# dynalo_v_dual.net
KiCad netlist of a schematic drawn in EAGLE
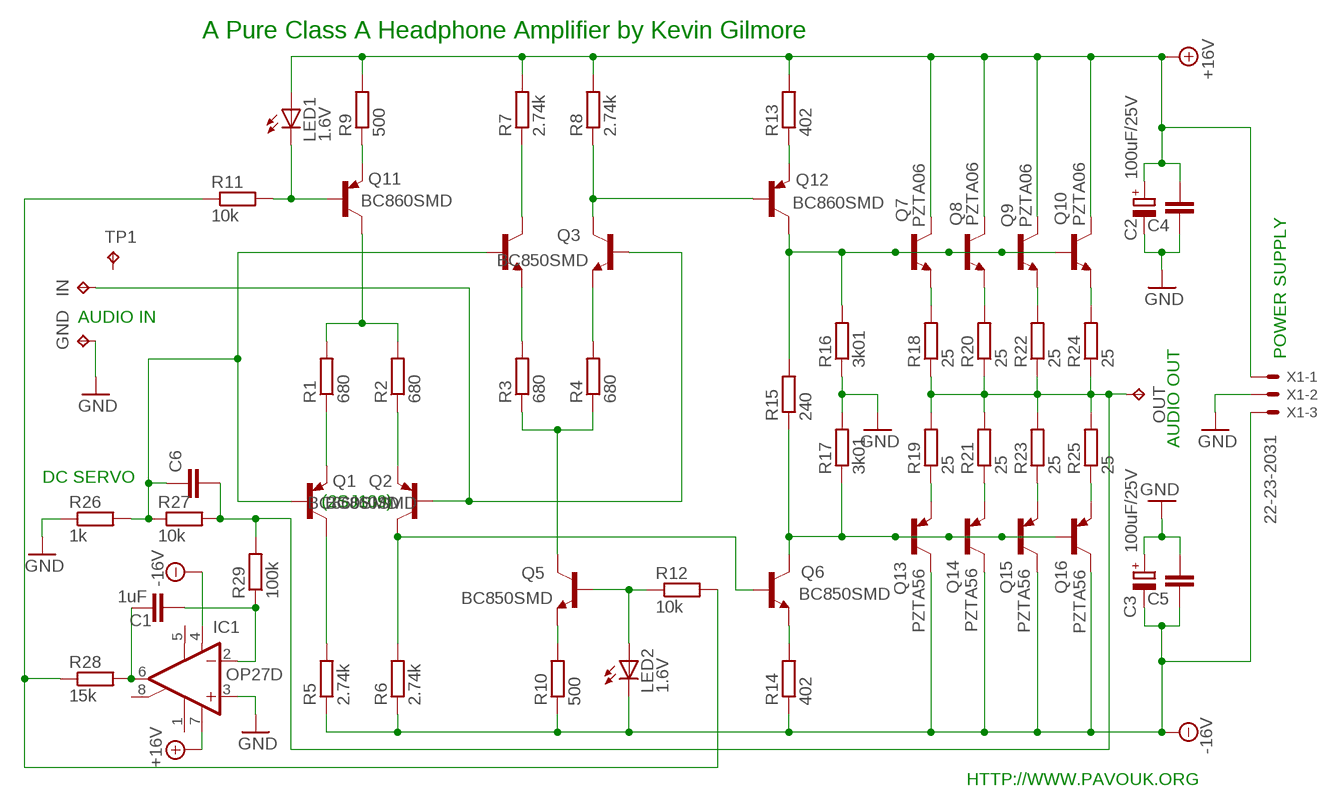
[diagram p0: schematic, sheet 1]

(export (version "E")
  (design (tool "Eeschema 10.0.6"))
  (components
    (comp (ref "C1")
      (value "1uF")
      (footprint "eagle-import:C1206")
      (libsource (lib "eagle-import") (part "C-EUC1206"))
    )
    (comp (ref "C2")
      (value "100uF/25V")
      (footprint "eagle-import:E3,5-8")
      (libsource (lib "eagle-import") (part "CPOL-EUE3.5-8"))
    )
    (comp (ref "C3")
      (value "100uF/25V")
      (footprint "eagle-import:E3,5-8")
      (libsource (lib "eagle-import") (part "CPOL-EUE3.5-8"))
    )
    (comp (ref "C4")
      (value "C-EUC1206")
      (footprint "eagle-import:C1206")
      (libsource (lib "eagle-import") (part "C-EUC1206"))
    )
    (comp (ref "C5")
      (value "C-EUC1206")
      (footprint "eagle-import:C1206")
      (libsource (lib "eagle-import") (part "C-EUC1206"))
    )
    (comp (ref "C6")
      (value "C-EUC1206")
      (footprint "eagle-import:C1206")
      (libsource (lib "eagle-import") (part "C-EUC1206"))
    )
    (comp (ref "GND")
      (value "TPPAD1-13")
      (footprint "eagle-import:P1-13")
      (libsource (lib "eagle-import") (part "TPPAD1-13"))
    )
    (comp (ref "IC1")
      (value "OP27D")
      (footprint "eagle-import:SO08")
      (libsource (lib "eagle-import") (part "OP27D"))
    )
    (comp (ref "IN")
      (value "TPPAD1-13")
      (footprint "eagle-import:P1-13")
      (libsource (lib "eagle-import") (part "TPPAD1-13"))
    )
    (comp (ref "LED1")
      (value "1.6V")
      (footprint "eagle-import:CHIPLED_1206")
      (libsource (lib "eagle-import") (part "LEDCHIPLED_1206"))
    )
    (comp (ref "LED2")
      (value "1.6V")
      (footprint "eagle-import:CHIPLED_1206")
      (libsource (lib "eagle-import") (part "LEDCHIPLED_1206"))
    )
    (comp (ref "OUT")
      (value "TPPAD1-13")
      (footprint "eagle-import:P1-13")
      (libsource (lib "eagle-import") (part "TPPAD1-13"))
    )
    (comp (ref "Q1")
      (value "BC860SMD")
      (footprint "eagle-import:SOT23-BEC")
      (libsource (lib "eagle-import") (part "BC860SMDC"))
    )
    (comp (ref "Q2")
      (value "BC860SMD")
      (footprint "eagle-import:SOT23-BEC")
      (libsource (lib "eagle-import") (part "BC860SMDC"))
    )
    (comp (ref "Q3")
      (value "BC850SMD")
      (footprint "eagle-import:SOT23-BEC")
      (libsource (lib "eagle-import") (part "BC850SMD"))
    )
    (comp (ref "Q4")
      (value "BC850SMD")
      (footprint "eagle-import:SOT23-BEC")
      (libsource (lib "eagle-import") (part "BC850SMD"))
    )
    (comp (ref "Q5")
      (value "BC850SMD")
      (footprint "eagle-import:SOT23-BEC")
      (libsource (lib "eagle-import") (part "BC850SMD"))
    )
    (comp (ref "Q6")
      (value "BC850SMD")
      (footprint "eagle-import:SOT23-BEC")
      (libsource (lib "eagle-import") (part "BC850SMD"))
    )
    (comp (ref "Q7")
      (value "PZTA06")
      (footprint "eagle-import:SOT223R_INFINEON")
      (libsource (lib "eagle-import") (part "PZTA06"))
    )
    (comp (ref "Q8")
      (value "PZTA06")
      (footprint "eagle-import:SOT223R_INFINEON")
      (libsource (lib "eagle-import") (part "PZTA06"))
    )
    (comp (ref "Q9")
      (value "PZTA06")
      (footprint "eagle-import:SOT223R_INFINEON")
      (libsource (lib "eagle-import") (part "PZTA06"))
    )
    (comp (ref "Q10")
      (value "PZTA06")
      (footprint "eagle-import:SOT223R_INFINEON")
      (libsource (lib "eagle-import") (part "PZTA06"))
    )
    (comp (ref "Q11")
      (value "BC860SMD")
      (footprint "eagle-import:SOT23-BEC")
      (libsource (lib "eagle-import") (part "BC860SMDC"))
    )
    (comp (ref "Q12")
      (value "BC860SMD")
      (footprint "eagle-import:SOT23-BEC")
      (libsource (lib "eagle-import") (part "BC860SMDC"))
    )
    (comp (ref "Q13")
      (value "PZTA56")
      (footprint "eagle-import:SOT223R_INFINEON")
      (libsource (lib "eagle-import") (part "PZTA56"))
    )
    (comp (ref "Q14")
      (value "PZTA56")
      (footprint "eagle-import:SOT223R_INFINEON")
      (libsource (lib "eagle-import") (part "PZTA56"))
    )
    (comp (ref "Q15")
      (value "PZTA56")
      (footprint "eagle-import:SOT223R_INFINEON")
      (libsource (lib "eagle-import") (part "PZTA56"))
    )
    (comp (ref "Q16")
      (value "PZTA56")
      (footprint "eagle-import:SOT223R_INFINEON")
      (libsource (lib "eagle-import") (part "PZTA56"))
    )
    (comp (ref "R1")
      (value "680")
      (footprint "eagle-import:MINI_MELF-0204W")
      (libsource (lib "eagle-import") (part "R-EU_MELF0204W"))
    )
    (comp (ref "R2")
      (value "680")
      (footprint "eagle-import:MINI_MELF-0204W")
      (libsource (lib "eagle-import") (part "R-EU_MELF0204W"))
    )
    (comp (ref "R3")
      (value "680")
      (footprint "eagle-import:MINI_MELF-0204W")
      (libsource (lib "eagle-import") (part "R-EU_MELF0204W"))
    )
    (comp (ref "R4")
      (value "680")
      (footprint "eagle-import:MINI_MELF-0204W")
      (libsource (lib "eagle-import") (part "R-EU_MELF0204W"))
    )
    (comp (ref "R5")
      (value "2.74k")
      (footprint "eagle-import:MINI_MELF-0204W")
      (libsource (lib "eagle-import") (part "R-EU_MELF0204W"))
    )
    (comp (ref "R6")
      (value "2.74k")
      (footprint "eagle-import:MINI_MELF-0204W")
      (libsource (lib "eagle-import") (part "R-EU_MELF0204W"))
    )
    (comp (ref "R7")
      (value "2.74k")
      (footprint "eagle-import:MINI_MELF-0204W")
      (libsource (lib "eagle-import") (part "R-EU_MELF0204W"))
    )
    (comp (ref "R8")
      (value "2.74k")
      (footprint "eagle-import:MINI_MELF-0204W")
      (libsource (lib "eagle-import") (part "R-EU_MELF0204W"))
    )
    (comp (ref "R9")
      (value "500")
      (footprint "eagle-import:MINI_MELF-0204W")
      (libsource (lib "eagle-import") (part "R-EU_MELF0204W"))
    )
    (comp (ref "R10")
      (value "500")
      (footprint "eagle-import:MINI_MELF-0204W")
      (libsource (lib "eagle-import") (part "R-EU_MELF0204W"))
    )
    (comp (ref "R11")
      (value "10k")
      (footprint "eagle-import:MINI_MELF-0204W")
      (libsource (lib "eagle-import") (part "R-EU_MELF0204W"))
    )
    (comp (ref "R12")
      (value "10k")
      (footprint "eagle-import:MINI_MELF-0204W")
      (libsource (lib "eagle-import") (part "R-EU_MELF0204W"))
    )
    (comp (ref "R13")
      (value "402")
      (footprint "eagle-import:MINI_MELF-0204W")
      (libsource (lib "eagle-import") (part "R-EU_MELF0204W"))
    )
    (comp (ref "R14")
      (value "402")
      (footprint "eagle-import:MINI_MELF-0204W")
      (libsource (lib "eagle-import") (part "R-EU_MELF0204W"))
    )
    (comp (ref "R15")
      (value "240")
      (footprint "eagle-import:MINI_MELF-0204W")
      (libsource (lib "eagle-import") (part "R-EU_MELF0204W"))
    )
    (comp (ref "R16")
      (value "3k01")
      (footprint "eagle-import:MINI_MELF-0204W")
      (libsource (lib "eagle-import") (part "R-EU_MELF0204W"))
    )
    (comp (ref "R17")
      (value "3k01")
      (footprint "eagle-import:MINI_MELF-0204W")
      (libsource (lib "eagle-import") (part "R-EU_MELF0204W"))
    )
    (comp (ref "R18")
      (value "25")
      (footprint "eagle-import:MINI_MELF-0204W")
      (libsource (lib "eagle-import") (part "R-EU_MELF0204W"))
    )
    (comp (ref "R19")
      (value "25")
      (footprint "eagle-import:MINI_MELF-0204W")
      (libsource (lib "eagle-import") (part "R-EU_MELF0204W"))
    )
    (comp (ref "R20")
      (value "25")
      (footprint "eagle-import:MINI_MELF-0204W")
      (libsource (lib "eagle-import") (part "R-EU_MELF0204W"))
    )
    (comp (ref "R21")
      (value "25")
      (footprint "eagle-import:MINI_MELF-0204W")
      (libsource (lib "eagle-import") (part "R-EU_MELF0204W"))
    )
    (comp (ref "R22")
      (value "25")
      (footprint "eagle-import:MINI_MELF-0204W")
      (libsource (lib "eagle-import") (part "R-EU_MELF0204W"))
    )
    (comp (ref "R23")
      (value "25")
      (footprint "eagle-import:MINI_MELF-0204W")
      (libsource (lib "eagle-import") (part "R-EU_MELF0204W"))
    )
    (comp (ref "R24")
      (value "25")
      (footprint "eagle-import:MINI_MELF-0204W")
      (libsource (lib "eagle-import") (part "R-EU_MELF0204W"))
    )
    (comp (ref "R25")
      (value "25")
      (footprint "eagle-import:MINI_MELF-0204W")
      (libsource (lib "eagle-import") (part "R-EU_MELF0204W"))
    )
    (comp (ref "R26")
      (value "1k")
      (footprint "eagle-import:MINI_MELF-0204W")
      (libsource (lib "eagle-import") (part "R-EU_MELF0204W"))
    )
    (comp (ref "R27")
      (value "10k")
      (footprint "eagle-import:MINI_MELF-0204W")
      (libsource (lib "eagle-import") (part "R-EU_MELF0204W"))
    )
    (comp (ref "R28")
      (value "15k")
      (footprint "eagle-import:MINI_MELF-0204W")
      (libsource (lib "eagle-import") (part "R-EU_MELF0204W"))
    )
    (comp (ref "R29")
      (value "100k")
      (footprint "eagle-import:MINI_MELF-0204W")
      (libsource (lib "eagle-import") (part "R-EU_MELF0204W"))
    )
    (comp (ref "TP1")
      (value "TPPAD1-13")
      (footprint "eagle-import:P1-13")
      (libsource (lib "eagle-import") (part "TPPAD1-13"))
    )
    (comp (ref "X1")
      (value "22-23-2031")
      (footprint "eagle-import:22-23-2031")
      (libsource (lib "eagle-import") (part "22-23-2031"))
    )
  )
  (nets
    (net (code "1") (name "+16V") (class "Default")
      (node (ref "C2") (pin "+") (pinfunction "+_+") (pintype "passive"))
      (node (ref "C4") (pin "2") (pinfunction "2_2") (pintype "passive"))
      (node (ref "IC1") (pin "7") (pinfunction "V+_7") (pintype "power_in"))
      (node (ref "LED1") (pin "A") (pinfunction "A_A") (pintype "passive"))
      (node (ref "Q10") (pin "2") (pinfunction "C_2") (pintype "passive"))
      (node (ref "Q10") (pin "4") (pinfunction "C_4") (pintype "passive"))
      (node (ref "Q7") (pin "2") (pinfunction "C_2") (pintype "passive"))
      (node (ref "Q7") (pin "4") (pinfunction "C_4") (pintype "passive"))
      (node (ref "Q8") (pin "2") (pinfunction "C_2") (pintype "passive"))
      (node (ref "Q8") (pin "4") (pinfunction "C_4") (pintype "passive"))
      (node (ref "Q9") (pin "2") (pinfunction "C_2") (pintype "passive"))
      (node (ref "Q9") (pin "4") (pinfunction "C_4") (pintype "passive"))
      (node (ref "R13") (pin "2") (pinfunction "2_2") (pintype "passive"))
      (node (ref "R7") (pin "2") (pinfunction "2_2") (pintype "passive"))
      (node (ref "R8") (pin "2") (pinfunction "2_2") (pintype "passive"))
      (node (ref "R9") (pin "2") (pinfunction "2_2") (pintype "passive"))
      (node (ref "X1") (pin "1") (pinfunction "S_1") (pintype "passive"))
    )
    (net (code "2") (name "-16V") (class "Default")
      (node (ref "C3") (pin "-") (pinfunction "-_-") (pintype "passive"))
      (node (ref "C5") (pin "1") (pinfunction "1_1") (pintype "passive"))
      (node (ref "IC1") (pin "4") (pinfunction "V-_4") (pintype "power_in"))
      (node (ref "LED2") (pin "C") (pinfunction "C_C") (pintype "passive"))
      (node (ref "Q13") (pin "2") (pinfunction "C_2") (pintype "passive"))
      (node (ref "Q13") (pin "4") (pinfunction "C_4") (pintype "passive"))
      (node (ref "Q14") (pin "2") (pinfunction "C_2") (pintype "passive"))
      (node (ref "Q14") (pin "4") (pinfunction "C_4") (pintype "passive"))
      (node (ref "Q15") (pin "2") (pinfunction "C_2") (pintype "passive"))
      (node (ref "Q15") (pin "4") (pinfunction "C_4") (pintype "passive"))
      (node (ref "Q16") (pin "2") (pinfunction "C_2") (pintype "passive"))
      (node (ref "Q16") (pin "4") (pinfunction "C_4") (pintype "passive"))
      (node (ref "R10") (pin "1") (pinfunction "1_1") (pintype "passive"))
      (node (ref "R14") (pin "1") (pinfunction "1_1") (pintype "passive"))
      (node (ref "R5") (pin "1") (pinfunction "1_1") (pintype "passive"))
      (node (ref "R6") (pin "1") (pinfunction "1_1") (pintype "passive"))
      (node (ref "X1") (pin "3") (pinfunction "S_3") (pintype "passive"))
    )
    (net (code "3") (name "GND") (class "Default")
      (node (ref "C2") (pin "-") (pinfunction "-_-") (pintype "passive"))
      (node (ref "C3") (pin "+") (pinfunction "+_+") (pintype "passive"))
      (node (ref "C4") (pin "1") (pinfunction "1_1") (pintype "passive"))
      (node (ref "C5") (pin "2") (pinfunction "2_2") (pintype "passive"))
      (node (ref "GND") (pin "TP") (pinfunction "TP_TP") (pintype "input"))
      (node (ref "IC1") (pin "3") (pinfunction "+IN_3") (pintype "input"))
      (node (ref "R16") (pin "1") (pinfunction "1_1") (pintype "passive"))
      (node (ref "R17") (pin "2") (pinfunction "2_2") (pintype "passive"))
      (node (ref "R26") (pin "1") (pinfunction "1_1") (pintype "passive"))
      (node (ref "X1") (pin "2") (pinfunction "S_2") (pintype "passive"))
    )
    (net (code "4") (name "Net-(C6-Pad1)") (class "Default")
      (node (ref "C6") (pin "1") (pinfunction "1_1") (pintype "passive"))
      (node (ref "Q1") (pin "B") (pinfunction "B_B") (pintype "passive"))
      (node (ref "Q4") (pin "B") (pinfunction "B_B") (pintype "passive"))
      (node (ref "R26") (pin "2") (pinfunction "2_2") (pintype "passive"))
      (node (ref "R27") (pin "1") (pinfunction "1_1") (pintype "passive"))
    )
    (net (code "5") (name "Net-(C6-Pad2)") (class "Default")
      (node (ref "C6") (pin "2") (pinfunction "2_2") (pintype "passive"))
      (node (ref "OUT") (pin "TP") (pinfunction "TP_TP") (pintype "input"))
      (node (ref "R18") (pin "1") (pinfunction "1_1") (pintype "passive"))
      (node (ref "R19") (pin "2") (pinfunction "2_2") (pintype "passive"))
      (node (ref "R20") (pin "1") (pinfunction "1_1") (pintype "passive"))
      (node (ref "R21") (pin "2") (pinfunction "2_2") (pintype "passive"))
      (node (ref "R22") (pin "1") (pinfunction "1_1") (pintype "passive"))
      (node (ref "R23") (pin "2") (pinfunction "2_2") (pintype "passive"))
      (node (ref "R24") (pin "1") (pinfunction "1_1") (pintype "passive"))
      (node (ref "R25") (pin "2") (pinfunction "2_2") (pintype "passive"))
      (node (ref "R27") (pin "2") (pinfunction "2_2") (pintype "passive"))
      (node (ref "R29") (pin "2") (pinfunction "2_2") (pintype "passive"))
    )
    (net (code "6") (name "Net-(IC1--IN)") (class "Default")
      (node (ref "C1") (pin "2") (pinfunction "2_2") (pintype "passive"))
      (node (ref "IC1") (pin "2") (pinfunction "-IN_2") (pintype "input"))
      (node (ref "R29") (pin "1") (pinfunction "1_1") (pintype "passive"))
    )
    (net (code "7") (name "Net-(IC1-OUT)") (class "Default")
      (node (ref "C1") (pin "1") (pinfunction "1_1") (pintype "passive"))
      (node (ref "IC1") (pin "6") (pinfunction "OUT_6") (pintype "output"))
      (node (ref "R28") (pin "2") (pinfunction "2_2") (pintype "passive"))
    )
    (net (code "8") (name "Net-(IN-PadTP)") (class "Default")
      (node (ref "IN") (pin "TP") (pinfunction "TP_TP") (pintype "input"))
      (node (ref "Q2") (pin "B") (pinfunction "B_B") (pintype "passive"))
      (node (ref "Q3") (pin "B") (pinfunction "B_B") (pintype "passive"))
    )
    (net (code "9") (name "Net-(LED1-PadC)") (class "Default")
      (node (ref "LED1") (pin "C") (pinfunction "C_C") (pintype "passive"))
      (node (ref "Q11") (pin "B") (pinfunction "B_B") (pintype "passive"))
      (node (ref "R11") (pin "2") (pinfunction "2_2") (pintype "passive"))
    )
    (net (code "10") (name "Net-(LED2-PadA)") (class "Default")
      (node (ref "LED2") (pin "A") (pinfunction "A_A") (pintype "passive"))
      (node (ref "Q5") (pin "B") (pinfunction "B_B") (pintype "passive"))
      (node (ref "R12") (pin "1") (pinfunction "1_1") (pintype "passive"))
    )
    (net (code "11") (name "Net-(Q1-PadC)") (class "Default")
      (node (ref "Q1") (pin "C") (pinfunction "C_C") (pintype "passive"))
      (node (ref "R5") (pin "2") (pinfunction "2_2") (pintype "passive"))
    )
    (net (code "12") (name "Net-(Q1-PadE)") (class "Default")
      (node (ref "Q1") (pin "E") (pinfunction "E_E") (pintype "passive"))
      (node (ref "R1") (pin "1") (pinfunction "1_1") (pintype "passive"))
    )
    (net (code "13") (name "Net-(Q2-PadC)") (class "Default")
      (node (ref "Q2") (pin "C") (pinfunction "C_C") (pintype "passive"))
      (node (ref "Q6") (pin "B") (pinfunction "B_B") (pintype "passive"))
      (node (ref "R6") (pin "2") (pinfunction "2_2") (pintype "passive"))
    )
    (net (code "14") (name "Net-(Q2-PadE)") (class "Default")
      (node (ref "Q2") (pin "E") (pinfunction "E_E") (pintype "passive"))
      (node (ref "R2") (pin "1") (pinfunction "1_1") (pintype "passive"))
    )
    (net (code "15") (name "Net-(Q3-PadE)") (class "Default")
      (node (ref "Q3") (pin "E") (pinfunction "E_E") (pintype "passive"))
      (node (ref "R4") (pin "2") (pinfunction "2_2") (pintype "passive"))
    )
    (net (code "16") (name "Net-(Q4-PadC)") (class "Default")
      (node (ref "Q4") (pin "C") (pinfunction "C_C") (pintype "passive"))
      (node (ref "R7") (pin "1") (pinfunction "1_1") (pintype "passive"))
    )
    (net (code "17") (name "Net-(Q4-PadE)") (class "Default")
      (node (ref "Q4") (pin "E") (pinfunction "E_E") (pintype "passive"))
      (node (ref "R3") (pin "2") (pinfunction "2_2") (pintype "passive"))
    )
    (net (code "18") (name "Net-(Q5-PadC)") (class "Default")
      (node (ref "Q5") (pin "C") (pinfunction "C_C") (pintype "passive"))
      (node (ref "R3") (pin "1") (pinfunction "1_1") (pintype "passive"))
      (node (ref "R4") (pin "1") (pinfunction "1_1") (pintype "passive"))
    )
    (net (code "19") (name "Net-(Q5-PadE)") (class "Default")
      (node (ref "Q5") (pin "E") (pinfunction "E_E") (pintype "passive"))
      (node (ref "R10") (pin "2") (pinfunction "2_2") (pintype "passive"))
    )
    (net (code "20") (name "Net-(Q6-PadE)") (class "Default")
      (node (ref "Q6") (pin "E") (pinfunction "E_E") (pintype "passive"))
      (node (ref "R14") (pin "2") (pinfunction "2_2") (pintype "passive"))
    )
    (net (code "21") (name "Net-(Q7-E)") (class "Default")
      (node (ref "Q7") (pin "3") (pinfunction "E_3") (pintype "passive"))
      (node (ref "R18") (pin "2") (pinfunction "2_2") (pintype "passive"))
    )
    (net (code "22") (name "Net-(Q8-E)") (class "Default")
      (node (ref "Q8") (pin "3") (pinfunction "E_3") (pintype "passive"))
      (node (ref "R20") (pin "2") (pinfunction "2_2") (pintype "passive"))
    )
    (net (code "23") (name "Net-(Q9-E)") (class "Default")
      (node (ref "Q9") (pin "3") (pinfunction "E_3") (pintype "passive"))
      (node (ref "R22") (pin "2") (pinfunction "2_2") (pintype "passive"))
    )
    (net (code "24") (name "Net-(Q10-B)") (class "Default")
      (node (ref "Q10") (pin "1") (pinfunction "B_1") (pintype "passive"))
      (node (ref "Q12") (pin "C") (pinfunction "C_C") (pintype "passive"))
      (node (ref "Q7") (pin "1") (pinfunction "B_1") (pintype "passive"))
      (node (ref "Q8") (pin "1") (pinfunction "B_1") (pintype "passive"))
      (node (ref "Q9") (pin "1") (pinfunction "B_1") (pintype "passive"))
      (node (ref "R15") (pin "2") (pinfunction "2_2") (pintype "passive"))
      (node (ref "R16") (pin "2") (pinfunction "2_2") (pintype "passive"))
    )
    (net (code "25") (name "Net-(Q10-E)") (class "Default")
      (node (ref "Q10") (pin "3") (pinfunction "E_3") (pintype "passive"))
      (node (ref "R24") (pin "2") (pinfunction "2_2") (pintype "passive"))
    )
    (net (code "26") (name "Net-(Q11-PadC)") (class "Default")
      (node (ref "Q11") (pin "C") (pinfunction "C_C") (pintype "passive"))
      (node (ref "R1") (pin "2") (pinfunction "2_2") (pintype "passive"))
      (node (ref "R2") (pin "2") (pinfunction "2_2") (pintype "passive"))
    )
    (net (code "27") (name "Net-(Q11-PadE)") (class "Default")
      (node (ref "Q11") (pin "E") (pinfunction "E_E") (pintype "passive"))
      (node (ref "R9") (pin "1") (pinfunction "1_1") (pintype "passive"))
    )
    (net (code "28") (name "Net-(Q12-PadB)") (class "Default")
      (node (ref "Q12") (pin "B") (pinfunction "B_B") (pintype "passive"))
      (node (ref "Q3") (pin "C") (pinfunction "C_C") (pintype "passive"))
      (node (ref "R8") (pin "1") (pinfunction "1_1") (pintype "passive"))
    )
    (net (code "29") (name "Net-(Q12-PadE)") (class "Default")
      (node (ref "Q12") (pin "E") (pinfunction "E_E") (pintype "passive"))
      (node (ref "R13") (pin "1") (pinfunction "1_1") (pintype "passive"))
    )
    (net (code "30") (name "Net-(Q13-B)") (class "Default")
      (node (ref "Q13") (pin "1") (pinfunction "B_1") (pintype "passive"))
      (node (ref "Q14") (pin "1") (pinfunction "B_1") (pintype "passive"))
      (node (ref "Q15") (pin "1") (pinfunction "B_1") (pintype "passive"))
      (node (ref "Q16") (pin "1") (pinfunction "B_1") (pintype "passive"))
      (node (ref "Q6") (pin "C") (pinfunction "C_C") (pintype "passive"))
      (node (ref "R15") (pin "1") (pinfunction "1_1") (pintype "passive"))
      (node (ref "R17") (pin "1") (pinfunction "1_1") (pintype "passive"))
    )
    (net (code "31") (name "Net-(Q13-E)") (class "Default")
      (node (ref "Q13") (pin "3") (pinfunction "E_3") (pintype "passive"))
      (node (ref "R19") (pin "1") (pinfunction "1_1") (pintype "passive"))
    )
    (net (code "32") (name "Net-(Q14-E)") (class "Default")
      (node (ref "Q14") (pin "3") (pinfunction "E_3") (pintype "passive"))
      (node (ref "R21") (pin "1") (pinfunction "1_1") (pintype "passive"))
    )
    (net (code "33") (name "Net-(Q15-E)") (class "Default")
      (node (ref "Q15") (pin "3") (pinfunction "E_3") (pintype "passive"))
      (node (ref "R23") (pin "1") (pinfunction "1_1") (pintype "passive"))
    )
    (net (code "34") (name "Net-(Q16-E)") (class "Default")
      (node (ref "Q16") (pin "3") (pinfunction "E_3") (pintype "passive"))
      (node (ref "R25") (pin "1") (pinfunction "1_1") (pintype "passive"))
    )
    (net (code "35") (name "Net-(R11-Pad1)") (class "Default")
      (node (ref "R11") (pin "1") (pinfunction "1_1") (pintype "passive"))
      (node (ref "R12") (pin "2") (pinfunction "2_2") (pintype "passive"))
      (node (ref "R28") (pin "1") (pinfunction "1_1") (pintype "passive"))
    )
    (net (code "36") (name "unconnected-(IC1-ON1-Pad1)") (class "Default")
      (node (ref "IC1") (pin "1") (pinfunction "ON1_1") (pintype "passive"))
    )
    (net (code "37") (name "unconnected-(IC1-ON2-Pad8)") (class "Default")
      (node (ref "IC1") (pin "8") (pinfunction "ON2_8") (pintype "passive"))
    )
    (net (code "38") (name "unconnected-(IC1-OPT-Pad5)") (class "Default")
      (node (ref "IC1") (pin "5") (pinfunction "OPT_5") (pintype "passive"))
    )
    (net (code "39") (name "unconnected-(TP1-PadTP)") (class "Default")
      (node (ref "TP1") (pin "TP") (pinfunction "TP_TP") (pintype "input"))
    )
  )
)
